# ad5941.net
KiCad netlist of a schematic drawn in Altium Designer
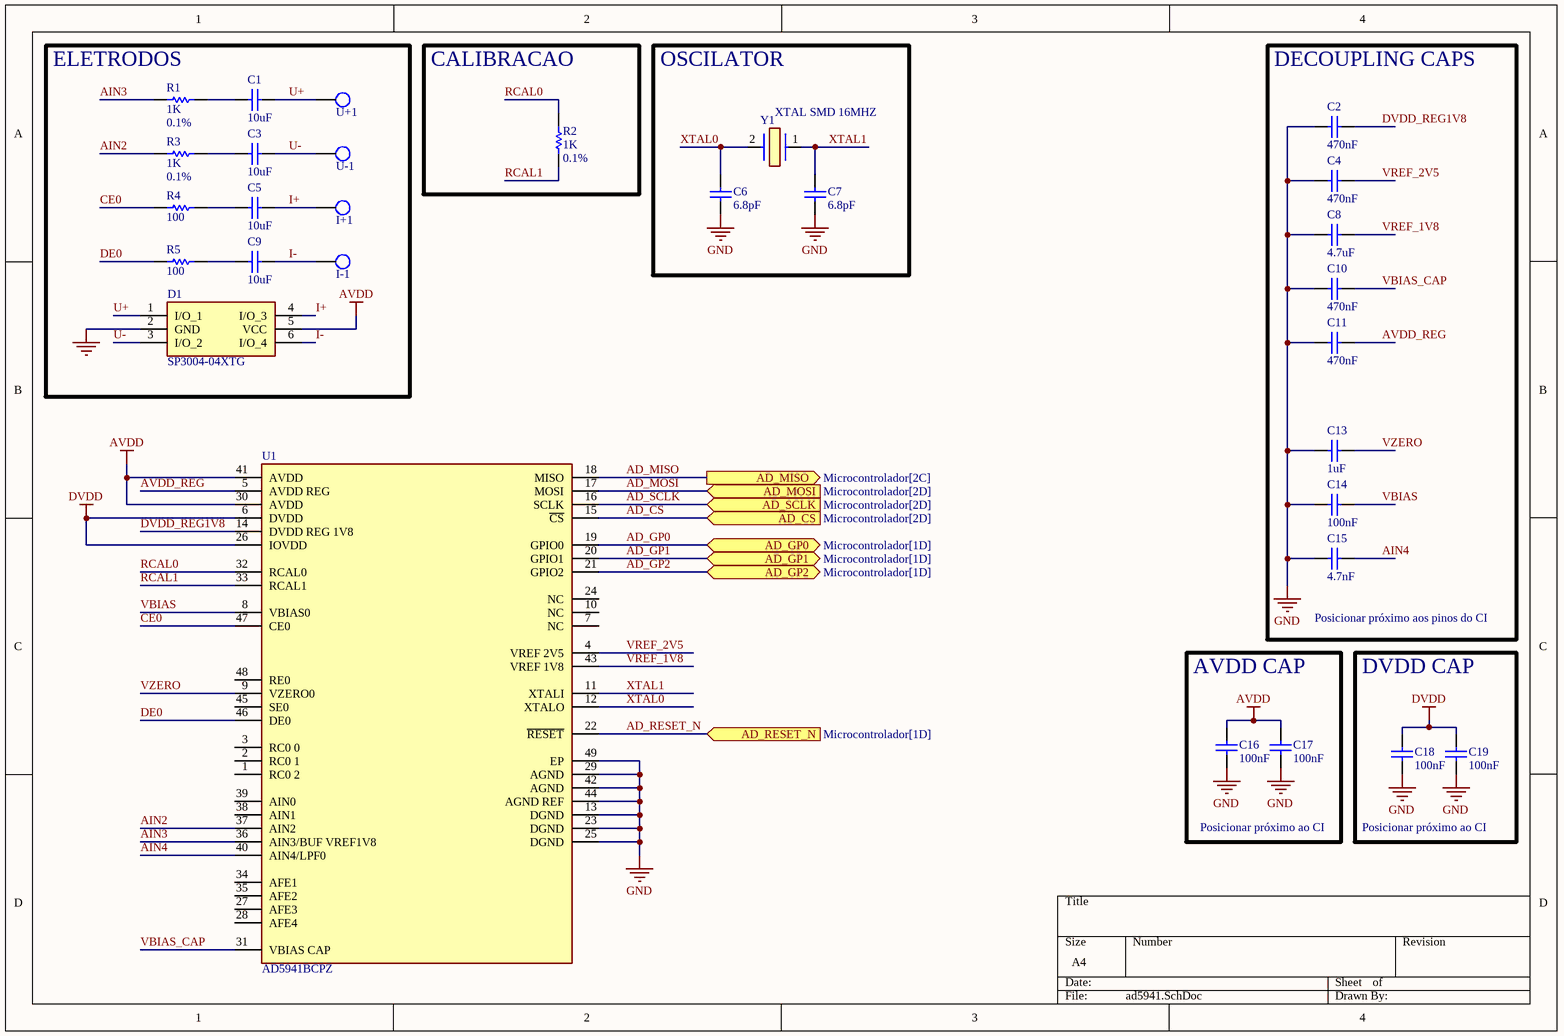
[diagram p0: ad5941.SchDoc]

(export (version "E")
  (design (tool "Eeschema 10.0.6"))
  (components
    (comp (ref "C1")
      (value "10uF")
      (footprint "CAP0805OK")
      (description "Multilayer Ceramic Capacitors MLCC - SMD/SMT 10 uF 10 VDC 10% 0805 X7R")
      (fields (field (name "TOLERANCE") "20%") (field (name "VOLTAGE") "50V"))
      (libsource (lib "BIB SCH GERAL") (part "CAP SMD CER 10UF 10V 0805"))
    )
    (comp (ref "C2")
      (value "470nF")
      (footprint "CAP0805OK")
      (fields
        (field (name "TOLERANCE") "10%")
        (field (name "VOLTAGE") "100V")
        (field (name "Comment") "CAP SMD CER 470NF 100V 0805")
      )
      (libsource (lib "BIB SCH GERAL") (part "CAP SMD CER 470NF 100V 0805"))
    )
    (comp (ref "C3")
      (value "10uF")
      (footprint "CAP0805OK")
      (description "Multilayer Ceramic Capacitors MLCC - SMD/SMT 10 uF 10 VDC 10% 0805 X7R")
      (fields (field (name "TOLERANCE") "20%") (field (name "VOLTAGE") "50V"))
      (libsource (lib "BIB SCH GERAL") (part "CAP SMD CER 10UF 10V 0805"))
    )
    (comp (ref "C4")
      (value "470nF")
      (footprint "CAP0805OK")
      (fields
        (field (name "TOLERANCE") "10%")
        (field (name "VOLTAGE") "100V")
        (field (name "Comment") "CAP SMD CER 470NF 100V 0805")
      )
      (libsource (lib "BIB SCH GERAL") (part "CAP SMD CER 470NF 100V 0805"))
    )
    (comp (ref "C5")
      (value "10uF")
      (footprint "CAP0805OK")
      (description "Multilayer Ceramic Capacitors MLCC - SMD/SMT 10 uF 10 VDC 10% 0805 X7R")
      (fields (field (name "TOLERANCE") "20%") (field (name "VOLTAGE") "50V"))
      (libsource (lib "BIB SCH GERAL") (part "CAP SMD CER 10UF 10V 0805"))
    )
    (comp (ref "C6")
      (value "6.8pF")
      (footprint "CAP0805OK")
      (fields
        (field (name "TOLERANCE") "10%")
        (field (name "VOLTAGE") "25V")
        (field (name "Comment") "CAP SMD CER 6.8PF 25V 0805")
      )
      (libsource (lib "BIB SCH GERAL") (part "CAP SMD CER 100NF 25V 0805"))
    )
    (comp (ref "C7")
      (value "6.8pF")
      (footprint "CAP0805OK")
      (fields
        (field (name "TOLERANCE") "10%")
        (field (name "VOLTAGE") "25V")
        (field (name "Comment") "CAP SMD CER 6.8PF 25V 0805")
      )
      (libsource (lib "BIB SCH GERAL") (part "CAP SMD CER 100NF 25V 0805"))
    )
    (comp (ref "C8")
      (value "4.7uF")
      (footprint "CAP0805OK")
      (fields
        (field (name "TOLERANCE") "10%")
        (field (name "VOLTAGE") "50V")
        (field (name "Comment") "CAP SMD CER 4.7UF 50V 0805")
      )
      (libsource (lib "BIB SCH GERAL") (part "CAP SMD CER 4.7UF 50V 0805"))
    )
    (comp (ref "C9")
      (value "10uF")
      (footprint "CAP0805OK")
      (description "Multilayer Ceramic Capacitors MLCC - SMD/SMT 10 uF 10 VDC 10% 0805 X7R")
      (fields (field (name "TOLERANCE") "20%") (field (name "VOLTAGE") "50V"))
      (libsource (lib "BIB SCH GERAL") (part "CAP SMD CER 10UF 10V 0805"))
    )
    (comp (ref "C10")
      (value "470nF")
      (footprint "CAP0805OK")
      (fields
        (field (name "TOLERANCE") "10%")
        (field (name "VOLTAGE") "100V")
        (field (name "Comment") "CAP SMD CER 470NF 100V 0805")
      )
      (libsource (lib "BIB SCH GERAL") (part "CAP SMD CER 470NF 100V 0805"))
    )
    (comp (ref "C11")
      (value "470nF")
      (footprint "CAP0805OK")
      (fields
        (field (name "TOLERANCE") "10%")
        (field (name "VOLTAGE") "100V")
        (field (name "Comment") "CAP SMD CER 470NF 100V 0805")
      )
      (libsource (lib "BIB SCH GERAL") (part "CAP SMD CER 470NF 100V 0805"))
    )
    (comp (ref "C13")
      (value "1uF")
      (footprint "CAP0805OK")
      (fields
        (field (name "TOLERANCE") "20%")
        (field (name "VOLTAGE") "10V")
        (field (name "Comment") "CAP SMD CER 1UF 10V 0805")
      )
      (libsource (lib "BIB SCH GERAL") (part "CAP SMD CER 1UF 10V 0805"))
    )
    (comp (ref "C14")
      (value "100nF")
      (footprint "CAP0805OK")
      (fields
        (field (name "TOLERANCE") "10%")
        (field (name "VOLTAGE") "25V")
        (field (name "Comment") "CAP SMD CER 100NF 25V 0805")
      )
      (libsource (lib "BIB SCH GERAL") (part "CAP SMD CER 100NF 25V 0805"))
    )
    (comp (ref "C15")
      (value "4.7nF")
      (footprint "CAP0805OK")
      (fields
        (field (name "TOLERANCE") "10%")
        (field (name "VOLTAGE") "25V")
        (field (name "Comment") "CAP SMD CER 4.7NF 25V 0805")
      )
      (libsource (lib "BIB SCH GERAL") (part "CAP SMD CER 100NF 25V 0805"))
    )
    (comp (ref "C16")
      (value "100nF")
      (footprint "CAP0805OK")
      (fields
        (field (name "TOLERANCE") "10%")
        (field (name "VOLTAGE") "25V")
        (field (name "Comment") "CAP SMD CER 100NF 25V 0805")
      )
      (libsource (lib "BIB SCH GERAL") (part "CAP SMD CER 100NF 25V 0805"))
    )
    (comp (ref "C17")
      (value "100nF")
      (footprint "CAP0805OK")
      (fields
        (field (name "TOLERANCE") "10%")
        (field (name "VOLTAGE") "25V")
        (field (name "Comment") "CAP SMD CER 100NF 25V 0805")
      )
      (libsource (lib "BIB SCH GERAL") (part "CAP SMD CER 100NF 25V 0805"))
    )
    (comp (ref "C18")
      (value "100nF")
      (footprint "CAP0805OK")
      (fields
        (field (name "TOLERANCE") "10%")
        (field (name "VOLTAGE") "25V")
        (field (name "Comment") "CAP SMD CER 100NF 25V 0805")
      )
      (libsource (lib "BIB SCH GERAL") (part "CAP SMD CER 100NF 25V 0805"))
    )
    (comp (ref "C19")
      (value "100nF")
      (footprint "CAP0805OK")
      (fields
        (field (name "TOLERANCE") "10%")
        (field (name "VOLTAGE") "25V")
        (field (name "Comment") "CAP SMD CER 100NF 25V 0805")
      )
      (libsource (lib "BIB SCH GERAL") (part "CAP SMD CER 100NF 25V 0805"))
    )
    (comp (ref "D1")
      (value "SP3004-04XTG")
      (footprint "LIB_GERAL_V2:SOTFL50P160X60-6N")
      (description "TVS Diode (Uni-directional)")
      (fields (field (name "MOUSER PART NUMBER") "576-SP3004-04XTG"))
      (libsource (lib "BIB SCH GERAL") (part "SP3004-04XTG"))
    )
    (comp (ref "I+1")
      (value "I+")
      (footprint "TEST POINT")
      (libsource (lib "BIB SCH GERAL") (part "TEST POINT"))
    )
    (comp (ref "I-1")
      (value "I-")
      (footprint "TEST POINT")
      (libsource (lib "BIB SCH GERAL") (part "TEST POINT"))
    )
    (comp (ref "R1")
      (value "1K")
      (footprint "res0805ok")
      (fields (field (name "TOLERANCE") "0.1%") (field (name "Comment") "RES SMD 1K6 0.1% 0805"))
      (libsource (lib "BIB SCH GERAL") (part "RES SMD 1K6 0.1% 0805"))
    )
    (comp (ref "R2")
      (value "1K")
      (footprint "res0805ok")
      (fields (field (name "TOLERANCE") "0.1%") (field (name "Comment") "RES SMD 1K 1% 0805"))
      (libsource (lib "BIB SCH GERAL") (part "RES SMD 1K 1% 0805"))
    )
    (comp (ref "R3")
      (value "1K")
      (footprint "res0805ok")
      (fields (field (name "TOLERANCE") "0.1%") (field (name "Comment") "RES SMD 1K6 0.1% 0805"))
      (libsource (lib "BIB SCH GERAL") (part "RES SMD 1K6 0.1% 0805"))
    )
    (comp (ref "R4")
      (value "100")
      (footprint "res0805ok")
      (fields (field (name "TOLERANCE") "1%") (field (name "Comment") "RES SMD 100R 1% 0805"))
      (libsource (lib "BIB SCH GERAL") (part "RES SMD 10R 1% 0805"))
    )
    (comp (ref "R5")
      (value "100")
      (footprint "res0805ok")
      (fields (field (name "TOLERANCE") "1%") (field (name "Comment") "RES SMD 100R 1% 0805"))
      (libsource (lib "BIB SCH GERAL") (part "RES SMD 10R 1% 0805"))
    )
    (comp (ref "U+1")
      (value "U+")
      (footprint "TEST POINT")
      (libsource (lib "BIB SCH GERAL") (part "TEST POINT"))
    )
    (comp (ref "U-1")
      (value "U-")
      (footprint "TEST POINT")
      (libsource (lib "BIB SCH GERAL") (part "TEST POINT"))
    )
    (comp (ref "U1")
      (value "AD5941BCPZ")
      (footprint "FP-CP-48-4-IPC_A")
      (description "BIO-IMPEDANCE & ELECTROCHEMICAL")
      (libsource (lib "Altium Content Vault") (part "6a54f8959a82146fbd7e10af4c03d01"))
    )
    (comp (ref "Y1")
      (value "XTAL SMD 16MHZ")
      (footprint "XTAL SMD 16MHZ")
      (description "Crystal or Oscillator")
      (fields
        (field (name "MANUFACTURER_PART_NUMBER") "XT9M20ANA16M")
        (field (name "MOUSER PART NUMBER") "73-XT49M1600-20")
      )
      (libsource (lib "BIB SCH GERAL") (part "XTAL SMD 16MHZ"))
    )
  )
  (nets
    (net (code "1") (name "/AD_CS") (class "Default")
      (node (ref "U1") (pin "15") (pinfunction "~{CS}_15") (pintype "passive"))
    )
    (net (code "2") (name "/AD_GP0") (class "Default")
      (node (ref "U1") (pin "19") (pinfunction "GPIO0_19") (pintype "passive"))
    )
    (net (code "3") (name "/AD_GP1") (class "Default")
      (node (ref "U1") (pin "20") (pinfunction "GPIO1_20") (pintype "passive"))
    )
    (net (code "4") (name "/AD_GP2") (class "Default")
      (node (ref "U1") (pin "21") (pinfunction "GPIO2_21") (pintype "passive"))
    )
    (net (code "5") (name "/AD_MISO") (class "Default")
      (node (ref "U1") (pin "18") (pinfunction "MISO_18") (pintype "passive"))
    )
    (net (code "6") (name "/AD_MOSI") (class "Default")
      (node (ref "U1") (pin "17") (pinfunction "MOSI_17") (pintype "passive"))
    )
    (net (code "7") (name "/AD_RESET_N") (class "Default")
      (node (ref "U1") (pin "22") (pinfunction "~{RESET}_22") (pintype "passive"))
    )
    (net (code "8") (name "/AD_SCLK") (class "Default")
      (node (ref "U1") (pin "16") (pinfunction "SCLK_16") (pintype "passive"))
    )
    (net (code "9") (name "/AIN2") (class "Default")
      (node (ref "R3") (pin "1") (pinfunction "1_1") (pintype "passive"))
      (node (ref "U1") (pin "37") (pinfunction "AIN2_37") (pintype "passive"))
    )
    (net (code "10") (name "/AIN3") (class "Default")
      (node (ref "R1") (pin "1") (pinfunction "1_1") (pintype "passive"))
      (node (ref "U1") (pin "36") (pinfunction "AIN3/BUF_VREF1V8_36") (pintype "passive"))
    )
    (net (code "11") (name "/AIN4") (class "Default")
      (node (ref "C15") (pin "1") (pinfunction "1_1") (pintype "passive"))
      (node (ref "U1") (pin "40") (pinfunction "AIN4/LPF0_40") (pintype "passive"))
    )
    (net (code "12") (name "/AVDD_REG") (class "Default")
      (node (ref "C11") (pin "2") (pinfunction "2_2") (pintype "passive"))
      (node (ref "U1") (pin "5") (pinfunction "AVDD_REG_5") (pintype "power_in"))
    )
    (net (code "13") (name "/CE0") (class "Default")
      (node (ref "R4") (pin "1") (pinfunction "1_1") (pintype "passive"))
      (node (ref "U1") (pin "47") (pinfunction "CE0_47") (pintype "passive"))
    )
    (net (code "14") (name "/DE0") (class "Default")
      (node (ref "R5") (pin "1") (pinfunction "1_1") (pintype "passive"))
      (node (ref "U1") (pin "46") (pinfunction "DE0_46") (pintype "passive"))
    )
    (net (code "15") (name "/DVDD_REG1V8") (class "Default")
      (node (ref "C2") (pin "2") (pinfunction "2_2") (pintype "passive"))
      (node (ref "U1") (pin "14") (pinfunction "DVDD_REG_1V8_14") (pintype "power_in"))
    )
    (net (code "16") (name "/I+") (class "Default")
      (node (ref "C5") (pin "2") (pinfunction "2_2") (pintype "passive"))
      (node (ref "D1") (pin "4") (pinfunction "I/O_3_4") (pintype "passive"))
      (node (ref "I+1") (pin "0") (pinfunction "0_0") (pintype "passive"))
    )
    (net (code "17") (name "/I-") (class "Default")
      (node (ref "C9") (pin "2") (pinfunction "2_2") (pintype "passive"))
      (node (ref "D1") (pin "6") (pinfunction "I/O_4_6") (pintype "passive"))
      (node (ref "I-1") (pin "0") (pinfunction "0_0") (pintype "passive"))
    )
    (net (code "18") (name "/RCAL0") (class "Default")
      (node (ref "R2") (pin "2") (pinfunction "2_2") (pintype "passive"))
      (node (ref "U1") (pin "32") (pinfunction "RCAL0_32") (pintype "passive"))
    )
    (net (code "19") (name "/RCAL1") (class "Default")
      (node (ref "R2") (pin "1") (pinfunction "1_1") (pintype "passive"))
      (node (ref "U1") (pin "33") (pinfunction "RCAL1_33") (pintype "passive"))
    )
    (net (code "20") (name "/U+") (class "Default")
      (node (ref "C1") (pin "2") (pinfunction "2_2") (pintype "passive"))
      (node (ref "D1") (pin "1") (pinfunction "I/O_1_1") (pintype "passive"))
      (node (ref "U+1") (pin "0") (pinfunction "0_0") (pintype "passive"))
    )
    (net (code "21") (name "/U-") (class "Default")
      (node (ref "C3") (pin "2") (pinfunction "2_2") (pintype "passive"))
      (node (ref "D1") (pin "3") (pinfunction "I/O_2_3") (pintype "passive"))
      (node (ref "U-1") (pin "0") (pinfunction "0_0") (pintype "passive"))
    )
    (net (code "22") (name "/VBIAS") (class "Default")
      (node (ref "C14") (pin "1") (pinfunction "1_1") (pintype "passive"))
      (node (ref "U1") (pin "8") (pinfunction "VBIAS0_8") (pintype "passive"))
    )
    (net (code "23") (name "/VBIAS_CAP") (class "Default")
      (node (ref "C10") (pin "2") (pinfunction "2_2") (pintype "passive"))
      (node (ref "U1") (pin "31") (pinfunction "VBIAS_CAP_31") (pintype "power_in"))
    )
    (net (code "24") (name "/VREF_1V8") (class "Default")
      (node (ref "C8") (pin "2") (pinfunction "2_2") (pintype "passive"))
      (node (ref "U1") (pin "43") (pinfunction "VREF_1V8_43") (pintype "power_in"))
    )
    (net (code "25") (name "/VREF_2V5") (class "Default")
      (node (ref "C4") (pin "2") (pinfunction "2_2") (pintype "passive"))
      (node (ref "U1") (pin "4") (pinfunction "VREF_2V5_4") (pintype "power_in"))
    )
    (net (code "26") (name "/VZERO") (class "Default")
      (node (ref "C13") (pin "2") (pinfunction "2_2") (pintype "passive"))
      (node (ref "U1") (pin "9") (pinfunction "VZERO0_9") (pintype "passive"))
    )
    (net (code "27") (name "/XTAL0") (class "Default")
      (node (ref "C6") (pin "1") (pinfunction "1_1") (pintype "passive"))
      (node (ref "U1") (pin "12") (pinfunction "XTALO_12") (pintype "passive"))
      (node (ref "Y1") (pin "2") (pinfunction "2_2") (pintype "passive"))
    )
    (net (code "28") (name "/XTAL1") (class "Default")
      (node (ref "C7") (pin "1") (pinfunction "1_1") (pintype "passive"))
      (node (ref "U1") (pin "11") (pinfunction "XTALI_11") (pintype "passive"))
      (node (ref "Y1") (pin "1") (pinfunction "1_1") (pintype "passive"))
    )
    (net (code "29") (name "AVDD") (class "Default")
      (node (ref "C16") (pin "1") (pinfunction "1_1") (pintype "passive"))
      (node (ref "C17") (pin "1") (pinfunction "1_1") (pintype "passive"))
      (node (ref "D1") (pin "5") (pinfunction "VCC_5") (pintype "passive"))
      (node (ref "U1") (pin "30") (pinfunction "AVDD_30") (pintype "power_in"))
      (node (ref "U1") (pin "41") (pinfunction "AVDD_41") (pintype "power_in"))
    )
    (net (code "30") (name "DVDD") (class "Default")
      (node (ref "C18") (pin "1") (pinfunction "1_1") (pintype "passive"))
      (node (ref "C19") (pin "1") (pinfunction "1_1") (pintype "passive"))
      (node (ref "U1") (pin "26") (pinfunction "IOVDD_26") (pintype "power_in"))
      (node (ref "U1") (pin "6") (pinfunction "DVDD_6") (pintype "power_in"))
    )
    (net (code "31") (name "GND") (class "Default")
      (node (ref "C10") (pin "1") (pinfunction "1_1") (pintype "passive"))
      (node (ref "C11") (pin "1") (pinfunction "1_1") (pintype "passive"))
      (node (ref "C13") (pin "1") (pinfunction "1_1") (pintype "passive"))
      (node (ref "C14") (pin "2") (pinfunction "2_2") (pintype "passive"))
      (node (ref "C15") (pin "2") (pinfunction "2_2") (pintype "passive"))
      (node (ref "C16") (pin "2") (pinfunction "2_2") (pintype "passive"))
      (node (ref "C17") (pin "2") (pinfunction "2_2") (pintype "passive"))
      (node (ref "C18") (pin "2") (pinfunction "2_2") (pintype "passive"))
      (node (ref "C19") (pin "2") (pinfunction "2_2") (pintype "passive"))
      (node (ref "C2") (pin "1") (pinfunction "1_1") (pintype "passive"))
      (node (ref "C4") (pin "1") (pinfunction "1_1") (pintype "passive"))
      (node (ref "C6") (pin "2") (pinfunction "2_2") (pintype "passive"))
      (node (ref "C7") (pin "2") (pinfunction "2_2") (pintype "passive"))
      (node (ref "C8") (pin "1") (pinfunction "1_1") (pintype "passive"))
      (node (ref "D1") (pin "2") (pinfunction "GND_2") (pintype "passive"))
      (node (ref "U1") (pin "13") (pinfunction "DGND_13") (pintype "power_in"))
      (node (ref "U1") (pin "23") (pinfunction "DGND_23") (pintype "power_in"))
      (node (ref "U1") (pin "25") (pinfunction "DGND_25") (pintype "power_in"))
      (node (ref "U1") (pin "29") (pinfunction "AGND_29") (pintype "power_in"))
      (node (ref "U1") (pin "42") (pinfunction "AGND_42") (pintype "power_in"))
      (node (ref "U1") (pin "44") (pinfunction "AGND_REF_44") (pintype "power_in"))
      (node (ref "U1") (pin "49") (pinfunction "EP_49") (pintype "passive"))
    )
    (net (code "32") (name "Net-(C1-Pad1)") (class "Default")
      (node (ref "C1") (pin "1") (pinfunction "1_1") (pintype "passive"))
      (node (ref "R1") (pin "2") (pinfunction "2_2") (pintype "passive"))
    )
    (net (code "33") (name "Net-(C3-Pad1)") (class "Default")
      (node (ref "C3") (pin "1") (pinfunction "1_1") (pintype "passive"))
      (node (ref "R3") (pin "2") (pinfunction "2_2") (pintype "passive"))
    )
    (net (code "34") (name "Net-(C5-Pad1)") (class "Default")
      (node (ref "C5") (pin "1") (pinfunction "1_1") (pintype "passive"))
      (node (ref "R4") (pin "2") (pinfunction "2_2") (pintype "passive"))
    )
    (net (code "35") (name "Net-(C9-Pad1)") (class "Default")
      (node (ref "C9") (pin "1") (pinfunction "1_1") (pintype "passive"))
      (node (ref "R5") (pin "2") (pinfunction "2_2") (pintype "passive"))
    )
    (net (code "36") (name "unconnected-(U1-AFE1-Pad34)") (class "Default")
      (node (ref "U1") (pin "34") (pinfunction "AFE1_34") (pintype "passive"))
    )
    (net (code "37") (name "unconnected-(U1-AFE2-Pad35)") (class "Default")
      (node (ref "U1") (pin "35") (pinfunction "AFE2_35") (pintype "passive"))
    )
    (net (code "38") (name "unconnected-(U1-AFE3-Pad27)") (class "Default")
      (node (ref "U1") (pin "27") (pinfunction "AFE3_27") (pintype "passive"))
    )
    (net (code "39") (name "unconnected-(U1-AFE4-Pad28)") (class "Default")
      (node (ref "U1") (pin "28") (pinfunction "AFE4_28") (pintype "passive"))
    )
    (net (code "40") (name "unconnected-(U1-AIN0-Pad39)") (class "Default")
      (node (ref "U1") (pin "39") (pinfunction "AIN0_39") (pintype "passive"))
    )
    (net (code "41") (name "unconnected-(U1-AIN1-Pad38)") (class "Default")
      (node (ref "U1") (pin "38") (pinfunction "AIN1_38") (pintype "passive"))
    )
    (net (code "42") (name "unconnected-(U1-NC-Pad7)") (class "Default")
      (node (ref "U1") (pin "7") (pinfunction "NC_7") (pintype "passive"))
    )
    (net (code "43") (name "unconnected-(U1-NC-Pad10)") (class "Default")
      (node (ref "U1") (pin "10") (pinfunction "NC_10") (pintype "passive"))
    )
    (net (code "44") (name "unconnected-(U1-NC-Pad24)") (class "Default")
      (node (ref "U1") (pin "24") (pinfunction "NC_24") (pintype "passive"))
    )
    (net (code "45") (name "unconnected-(U1-RC0_0-Pad3)") (class "Default")
      (node (ref "U1") (pin "3") (pinfunction "RC0_0_3") (pintype "passive"))
    )
    (net (code "46") (name "unconnected-(U1-RC0_1-Pad2)") (class "Default")
      (node (ref "U1") (pin "2") (pinfunction "RC0_1_2") (pintype "passive"))
    )
    (net (code "47") (name "unconnected-(U1-RC0_2-Pad1)") (class "Default")
      (node (ref "U1") (pin "1") (pinfunction "RC0_2_1") (pintype "passive"))
    )
    (net (code "48") (name "unconnected-(U1-RE0-Pad48)") (class "Default")
      (node (ref "U1") (pin "48") (pinfunction "RE0_48") (pintype "passive"))
    )
    (net (code "49") (name "unconnected-(U1-SE0-Pad45)") (class "Default")
      (node (ref "U1") (pin "45") (pinfunction "SE0_45") (pintype "passive"))
    )
  )
)
